# Advantech-Wise-1530-v1_0_0.net
KiCad netlist of a schematic drawn in EAGLE
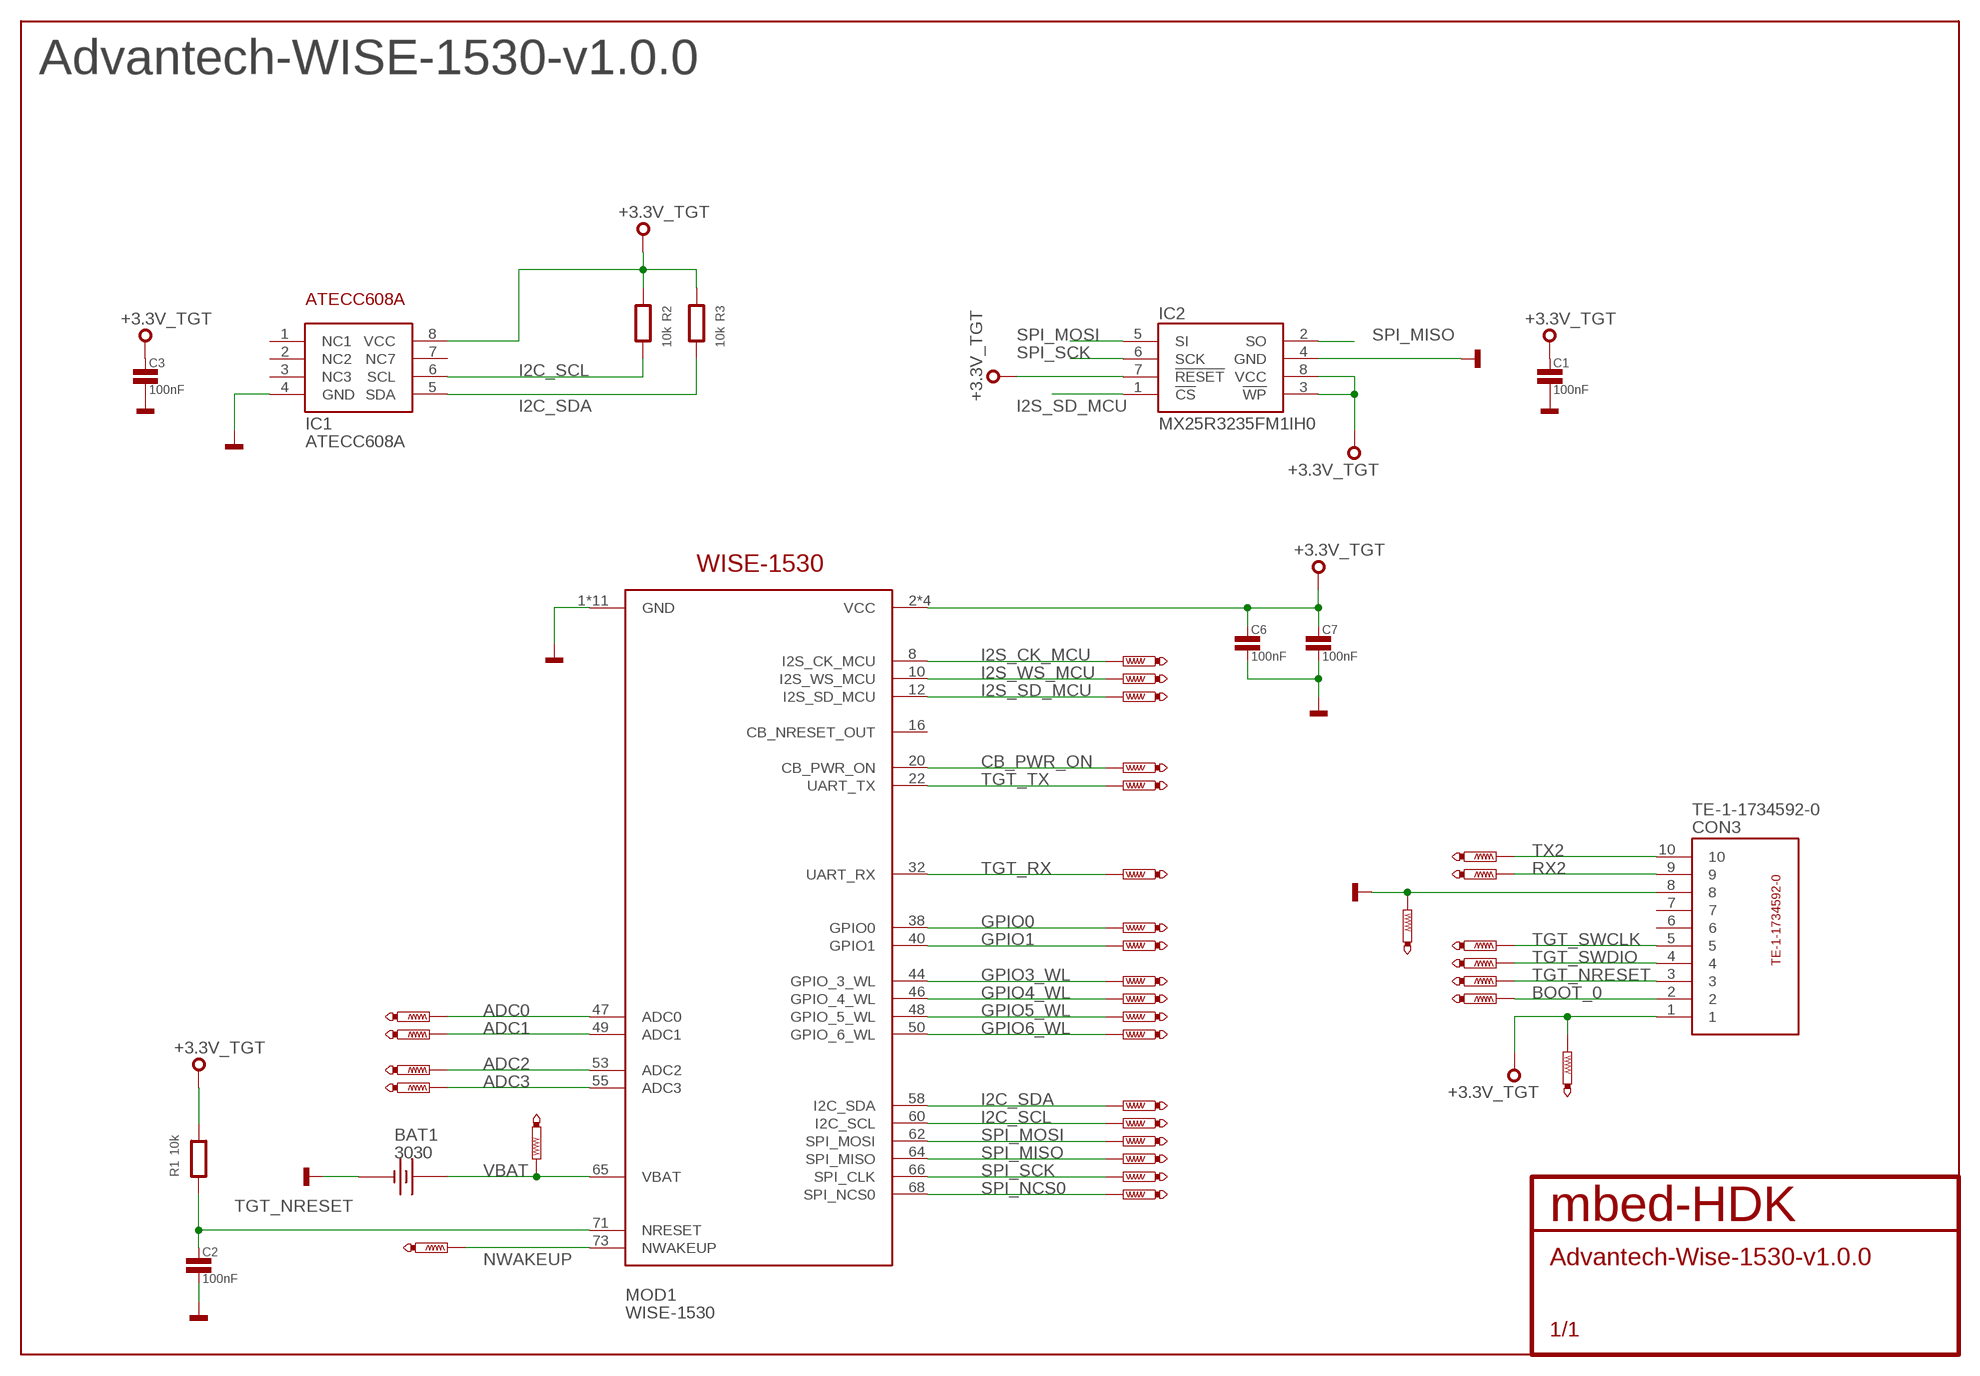
[diagram p0: schematic, sheet 1]

(export (version "E")
  (design (tool "Eeschema 10.0.6"))
  (components
    (comp (ref "BAT1")
      (value "3030")
      (footprint "eagle-import:3030")
      (fields (field (name "MF") "Keystone"))
      (libsource (lib "eagle-import") (part "3030"))
    )
    (comp (ref "C1")
      (value "100nF")
      (footprint "eagle-import:0603")
      (libsource (lib "eagle-import") (part "C0603"))
    )
    (comp (ref "C2")
      (value "100nF")
      (footprint "eagle-import:0603")
      (libsource (lib "eagle-import") (part "C0603"))
    )
    (comp (ref "C3")
      (value "100nF")
      (footprint "eagle-import:0603")
      (libsource (lib "eagle-import") (part "C0603"))
    )
    (comp (ref "C6")
      (value "100nF")
      (footprint "eagle-import:0603")
      (libsource (lib "eagle-import") (part "C0603"))
    )
    (comp (ref "C7")
      (value "100nF")
      (footprint "eagle-import:0603")
      (libsource (lib "eagle-import") (part "C0603"))
    )
    (comp (ref "CON3")
      (value "TE-1-1734592-0")
      (footprint "eagle-import:TE-1-1734592-0")
      (fields (field (name "MF") "TE Connectivity"))
      (libsource (lib "eagle-import") (part "TE-1-1734592-0"))
    )
    (comp (ref "IC1")
      (value "ATECC608A")
      (footprint "eagle-import:SO8")
      (fields (field (name "MF") "Atmel"))
      (libsource (lib "eagle-import") (part "ATECC608A"))
    )
    (comp (ref "IC2")
      (value "MX25R3235FM1IH0")
      (footprint "eagle-import:SO8")
      (fields (field (name "MF") "Macronix"))
      (libsource (lib "eagle-import") (part "MX25R3235FM1IH0"))
    )
    (comp (ref "MOD1")
      (value "WISE-1530")
      (footprint "eagle-import:MDT420E02001")
      (fields (field (name "MF") "Amphenol"))
      (libsource (lib "eagle-import") (part "WISE-1530"))
    )
    (comp (ref "R1")
      (value "10k")
      (footprint "eagle-import:0603")
      (libsource (lib "eagle-import") (part "R0603"))
    )
    (comp (ref "R2")
      (value "10k")
      (footprint "eagle-import:0603")
      (libsource (lib "eagle-import") (part "R0603"))
    )
    (comp (ref "R3")
      (value "10k")
      (footprint "eagle-import:0603")
      (libsource (lib "eagle-import") (part "R0603"))
    )
    (comp (ref "TP3")
      (value "PTR1TP08R")
      (footprint "eagle-import:TP08R")
      (libsource (lib "eagle-import") (part "PTR1TP08R"))
    )
    (comp (ref "TP4")
      (value "PTR1TP08R")
      (footprint "eagle-import:TP08R")
      (libsource (lib "eagle-import") (part "PTR1TP08R"))
    )
    (comp (ref "TP5")
      (value "PTR1TP08R")
      (footprint "eagle-import:TP08R")
      (libsource (lib "eagle-import") (part "PTR1TP08R"))
    )
    (comp (ref "TP6")
      (value "PTR1TP08R")
      (footprint "eagle-import:TP08R")
      (libsource (lib "eagle-import") (part "PTR1TP08R"))
    )
    (comp (ref "TP7")
      (value "PTR1TP08R")
      (footprint "eagle-import:TP08R")
      (libsource (lib "eagle-import") (part "PTR1TP08R"))
    )
    (comp (ref "TP8")
      (value "PTR1TP08R")
      (footprint "eagle-import:TP08R")
      (libsource (lib "eagle-import") (part "PTR1TP08R"))
    )
    (comp (ref "TP9")
      (value "PTR1TP08R")
      (footprint "eagle-import:TP08R")
      (libsource (lib "eagle-import") (part "PTR1TP08R"))
    )
    (comp (ref "TP10")
      (value "PTR1TP08R")
      (footprint "eagle-import:TP08R")
      (libsource (lib "eagle-import") (part "PTR1TP08R"))
    )
    (comp (ref "TP11")
      (value "PTR1TP08R")
      (footprint "eagle-import:TP08R")
      (libsource (lib "eagle-import") (part "PTR1TP08R"))
    )
    (comp (ref "TP12")
      (value "PTR1TP08R")
      (footprint "eagle-import:TP08R")
      (libsource (lib "eagle-import") (part "PTR1TP08R"))
    )
    (comp (ref "TP13")
      (value "PTR1TP08R")
      (footprint "eagle-import:TP08R")
      (libsource (lib "eagle-import") (part "PTR1TP08R"))
    )
    (comp (ref "TP14")
      (value "PTR1TP08R")
      (footprint "eagle-import:TP08R")
      (libsource (lib "eagle-import") (part "PTR1TP08R"))
    )
    (comp (ref "TP15")
      (value "PTR1TP08R")
      (footprint "eagle-import:TP08R")
      (libsource (lib "eagle-import") (part "PTR1TP08R"))
    )
    (comp (ref "TP16")
      (value "PTR1TP08R")
      (footprint "eagle-import:TP08R")
      (libsource (lib "eagle-import") (part "PTR1TP08R"))
    )
    (comp (ref "TP17")
      (value "PTR1TP08R")
      (footprint "eagle-import:TP08R")
      (libsource (lib "eagle-import") (part "PTR1TP08R"))
    )
    (comp (ref "TP18")
      (value "PTR1TP08R")
      (footprint "eagle-import:TP08R")
      (libsource (lib "eagle-import") (part "PTR1TP08R"))
    )
    (comp (ref "TP19")
      (value "PTR1TP08R")
      (footprint "eagle-import:TP08R")
      (libsource (lib "eagle-import") (part "PTR1TP08R"))
    )
    (comp (ref "TP20")
      (value "PTR1TP08R")
      (footprint "eagle-import:TP08R")
      (libsource (lib "eagle-import") (part "PTR1TP08R"))
    )
    (comp (ref "TP21")
      (value "PTR1TP08R")
      (footprint "eagle-import:TP08R")
      (libsource (lib "eagle-import") (part "PTR1TP08R"))
    )
    (comp (ref "TP22")
      (value "PTR1TP08R")
      (footprint "eagle-import:TP08R")
      (libsource (lib "eagle-import") (part "PTR1TP08R"))
    )
    (comp (ref "TP23")
      (value "PTR1TP08R")
      (footprint "eagle-import:TP08R")
      (libsource (lib "eagle-import") (part "PTR1TP08R"))
    )
    (comp (ref "TP24")
      (value "PTR1TP08R")
      (footprint "eagle-import:TP08R")
      (libsource (lib "eagle-import") (part "PTR1TP08R"))
    )
    (comp (ref "TP25")
      (value "PTR1TP08R")
      (footprint "eagle-import:TP08R")
      (libsource (lib "eagle-import") (part "PTR1TP08R"))
    )
    (comp (ref "TP26")
      (value "PTR1TP08R")
      (footprint "eagle-import:TP08R")
      (libsource (lib "eagle-import") (part "PTR1TP08R"))
    )
    (comp (ref "TP27")
      (value "PTR1TP08R")
      (footprint "eagle-import:TP08R")
      (libsource (lib "eagle-import") (part "PTR1TP08R"))
    )
    (comp (ref "TP28")
      (value "PTR1TP08R")
      (footprint "eagle-import:TP08R")
      (libsource (lib "eagle-import") (part "PTR1TP08R"))
    )
    (comp (ref "TP29")
      (value "PTR1TP08R")
      (footprint "eagle-import:TP08R")
      (libsource (lib "eagle-import") (part "PTR1TP08R"))
    )
    (comp (ref "TP30")
      (value "PTR1TP08R")
      (footprint "eagle-import:TP08R")
      (libsource (lib "eagle-import") (part "PTR1TP08R"))
    )
    (comp (ref "TP31")
      (value "PTR1TP08R")
      (footprint "eagle-import:TP08R")
      (libsource (lib "eagle-import") (part "PTR1TP08R"))
    )
    (comp (ref "TP32")
      (value "PTR1TP08R")
      (footprint "eagle-import:TP08R")
      (libsource (lib "eagle-import") (part "PTR1TP08R"))
    )
    (comp (ref "TP33")
      (value "PTR1TP08R")
      (footprint "eagle-import:TP08R")
      (libsource (lib "eagle-import") (part "PTR1TP08R"))
    )
    (comp (ref "TP34")
      (value "PTR1TP08R")
      (footprint "eagle-import:TP08R")
      (libsource (lib "eagle-import") (part "PTR1TP08R"))
    )
  )
  (nets
    (net (code "1") (name "+3.3V_TGT") (class "Default")
      (node (ref "C1") (pin "1") (pinfunction "P$1_1") (pintype "passive"))
      (node (ref "C3") (pin "1") (pinfunction "P$1_1") (pintype "passive"))
      (node (ref "C6") (pin "1") (pinfunction "P$1_1") (pintype "passive"))
      (node (ref "C7") (pin "1") (pinfunction "P$1_1") (pintype "passive"))
      (node (ref "CON3") (pin "1") (pinfunction "1_1") (pintype "bidirectional"))
      (node (ref "IC1") (pin "8") (pinfunction "VCC_8") (pintype "bidirectional"))
      (node (ref "IC2") (pin "3") (pinfunction "~{WP}_3") (pintype "bidirectional"))
      (node (ref "IC2") (pin "7") (pinfunction "~{RESET}_7") (pintype "bidirectional"))
      (node (ref "IC2") (pin "8") (pinfunction "VCC_8") (pintype "bidirectional"))
      (node (ref "MOD1") (pin "2") (pinfunction "VCC_2") (pintype "bidirectional"))
      (node (ref "MOD1") (pin "4") (pinfunction "VCC_4") (pintype "bidirectional"))
      (node (ref "MOD1") (pin "72") (pinfunction "VCC_72") (pintype "bidirectional"))
      (node (ref "MOD1") (pin "74") (pinfunction "VCC_74") (pintype "bidirectional"))
      (node (ref "R1") (pin "2") (pinfunction "P$2_2") (pintype "passive"))
      (node (ref "R2") (pin "1") (pinfunction "P$1_1") (pintype "passive"))
      (node (ref "R3") (pin "1") (pinfunction "P$1_1") (pintype "passive"))
      (node (ref "TP12") (pin "TP") (pinfunction "TP_TP") (pintype "input"))
    )
    (net (code "2") (name "/ADC0") (class "Default")
      (node (ref "MOD1") (pin "47") (pinfunction "ADC0_47") (pintype "bidirectional"))
      (node (ref "TP29") (pin "TP") (pinfunction "TP_TP") (pintype "input"))
    )
    (net (code "3") (name "/ADC1") (class "Default")
      (node (ref "MOD1") (pin "49") (pinfunction "ADC1_49") (pintype "bidirectional"))
      (node (ref "TP30") (pin "TP") (pinfunction "TP_TP") (pintype "input"))
    )
    (net (code "4") (name "/ADC2") (class "Default")
      (node (ref "MOD1") (pin "53") (pinfunction "ADC2_53") (pintype "bidirectional"))
      (node (ref "TP31") (pin "TP") (pinfunction "TP_TP") (pintype "input"))
    )
    (net (code "5") (name "/ADC3") (class "Default")
      (node (ref "MOD1") (pin "55") (pinfunction "ADC3_55") (pintype "bidirectional"))
      (node (ref "TP32") (pin "TP") (pinfunction "TP_TP") (pintype "input"))
    )
    (net (code "6") (name "/BOOT_0") (class "Default")
      (node (ref "CON3") (pin "2") (pinfunction "2_2") (pintype "bidirectional"))
      (node (ref "TP8") (pin "TP") (pinfunction "TP_TP") (pintype "input"))
    )
    (net (code "7") (name "/CB_PWR_ON") (class "Default")
      (node (ref "MOD1") (pin "20") (pinfunction "CB_PWR_ON_20") (pintype "bidirectional"))
      (node (ref "TP14") (pin "TP") (pinfunction "TP_TP") (pintype "input"))
    )
    (net (code "8") (name "/GPIO0") (class "Default")
      (node (ref "MOD1") (pin "38") (pinfunction "GPIO0_38") (pintype "bidirectional"))
      (node (ref "TP27") (pin "TP") (pinfunction "TP_TP") (pintype "input"))
    )
    (net (code "9") (name "/GPIO1") (class "Default")
      (node (ref "MOD1") (pin "40") (pinfunction "GPIO1_40") (pintype "bidirectional"))
      (node (ref "TP26") (pin "TP") (pinfunction "TP_TP") (pintype "input"))
    )
    (net (code "10") (name "/GPIO3_WL") (class "Default")
      (node (ref "MOD1") (pin "44") (pinfunction "GPIO_3_WL_44") (pintype "bidirectional"))
      (node (ref "TP25") (pin "TP") (pinfunction "TP_TP") (pintype "input"))
    )
    (net (code "11") (name "/GPIO4_WL") (class "Default")
      (node (ref "MOD1") (pin "46") (pinfunction "GPIO_4_WL_46") (pintype "bidirectional"))
      (node (ref "TP24") (pin "TP") (pinfunction "TP_TP") (pintype "input"))
    )
    (net (code "12") (name "/GPIO5_WL") (class "Default")
      (node (ref "MOD1") (pin "48") (pinfunction "GPIO_5_WL_48") (pintype "bidirectional"))
      (node (ref "TP23") (pin "TP") (pinfunction "TP_TP") (pintype "input"))
    )
    (net (code "13") (name "/GPIO6_WL") (class "Default")
      (node (ref "MOD1") (pin "50") (pinfunction "GPIO_6_WL_50") (pintype "bidirectional"))
      (node (ref "TP22") (pin "TP") (pinfunction "TP_TP") (pintype "input"))
    )
    (net (code "14") (name "/I2C_SCL") (class "Default")
      (node (ref "IC1") (pin "6") (pinfunction "SCL_6") (pintype "bidirectional"))
      (node (ref "MOD1") (pin "60") (pinfunction "I2C_SCL_60") (pintype "bidirectional"))
      (node (ref "R2") (pin "2") (pinfunction "P$2_2") (pintype "passive"))
      (node (ref "TP20") (pin "TP") (pinfunction "TP_TP") (pintype "input"))
    )
    (net (code "15") (name "/I2C_SDA") (class "Default")
      (node (ref "IC1") (pin "5") (pinfunction "SDA_5") (pintype "bidirectional"))
      (node (ref "MOD1") (pin "58") (pinfunction "I2C_SDA_58") (pintype "bidirectional"))
      (node (ref "R3") (pin "2") (pinfunction "P$2_2") (pintype "passive"))
      (node (ref "TP21") (pin "TP") (pinfunction "TP_TP") (pintype "input"))
    )
    (net (code "16") (name "/I2S_CK_MCU") (class "Default")
      (node (ref "MOD1") (pin "8") (pinfunction "I2S_CK_MCU_8") (pintype "bidirectional"))
      (node (ref "TP9") (pin "TP") (pinfunction "TP_TP") (pintype "input"))
    )
    (net (code "17") (name "/I2S_SD_MCU") (class "Default")
      (node (ref "IC2") (pin "1") (pinfunction "~{CS}_1") (pintype "bidirectional"))
      (node (ref "MOD1") (pin "12") (pinfunction "I2S_SD_MCU_12") (pintype "bidirectional"))
      (node (ref "TP11") (pin "TP") (pinfunction "TP_TP") (pintype "input"))
    )
    (net (code "18") (name "/I2S_WS_MCU") (class "Default")
      (node (ref "MOD1") (pin "10") (pinfunction "I2S_WS_MCU_10") (pintype "bidirectional"))
      (node (ref "TP10") (pin "TP") (pinfunction "TP_TP") (pintype "input"))
    )
    (net (code "19") (name "/NWAKEUP") (class "Default")
      (node (ref "MOD1") (pin "73") (pinfunction "NWAKEUP_73") (pintype "bidirectional"))
      (node (ref "TP34") (pin "TP") (pinfunction "TP_TP") (pintype "input"))
    )
    (net (code "20") (name "/RX2") (class "Default")
      (node (ref "CON3") (pin "9") (pinfunction "9_9") (pintype "bidirectional"))
      (node (ref "TP6") (pin "TP") (pinfunction "TP_TP") (pintype "input"))
    )
    (net (code "21") (name "/SPI_MISO") (class "Default")
      (node (ref "IC2") (pin "2") (pinfunction "SO_2") (pintype "bidirectional"))
      (node (ref "MOD1") (pin "64") (pinfunction "SPI_MISO_64") (pintype "bidirectional"))
      (node (ref "TP18") (pin "TP") (pinfunction "TP_TP") (pintype "input"))
    )
    (net (code "22") (name "/SPI_MOSI") (class "Default")
      (node (ref "IC2") (pin "5") (pinfunction "SI_5") (pintype "bidirectional"))
      (node (ref "MOD1") (pin "62") (pinfunction "SPI_MOSI_62") (pintype "bidirectional"))
      (node (ref "TP19") (pin "TP") (pinfunction "TP_TP") (pintype "input"))
    )
    (net (code "23") (name "/SPI_NCS0") (class "Default")
      (node (ref "MOD1") (pin "68") (pinfunction "SPI_NCS0_68") (pintype "bidirectional"))
      (node (ref "TP16") (pin "TP") (pinfunction "TP_TP") (pintype "input"))
    )
    (net (code "24") (name "/SPI_SCK") (class "Default")
      (node (ref "IC2") (pin "6") (pinfunction "SCK_6") (pintype "bidirectional"))
      (node (ref "MOD1") (pin "66") (pinfunction "SPI_CLK_66") (pintype "bidirectional"))
      (node (ref "TP17") (pin "TP") (pinfunction "TP_TP") (pintype "input"))
    )
    (net (code "25") (name "/TGT_NRESET") (class "Default")
      (node (ref "C2") (pin "1") (pinfunction "P$1_1") (pintype "passive"))
      (node (ref "CON3") (pin "3") (pinfunction "3_3") (pintype "bidirectional"))
      (node (ref "MOD1") (pin "71") (pinfunction "NRESET_71") (pintype "bidirectional"))
      (node (ref "R1") (pin "1") (pinfunction "P$1_1") (pintype "passive"))
      (node (ref "TP5") (pin "TP") (pinfunction "TP_TP") (pintype "input"))
    )
    (net (code "26") (name "/TGT_RX") (class "Default")
      (node (ref "MOD1") (pin "32") (pinfunction "UART_RX_32") (pintype "bidirectional"))
      (node (ref "TP28") (pin "TP") (pinfunction "TP_TP") (pintype "input"))
    )
    (net (code "27") (name "/TGT_SWCLK") (class "Default")
      (node (ref "CON3") (pin "5") (pinfunction "5_5") (pintype "bidirectional"))
      (node (ref "TP3") (pin "TP") (pinfunction "TP_TP") (pintype "input"))
    )
    (net (code "28") (name "/TGT_SWDIO") (class "Default")
      (node (ref "CON3") (pin "4") (pinfunction "4_4") (pintype "bidirectional"))
      (node (ref "TP4") (pin "TP") (pinfunction "TP_TP") (pintype "input"))
    )
    (net (code "29") (name "/TGT_TX") (class "Default")
      (node (ref "MOD1") (pin "22") (pinfunction "UART_TX_22") (pintype "bidirectional"))
      (node (ref "TP15") (pin "TP") (pinfunction "TP_TP") (pintype "input"))
    )
    (net (code "30") (name "/TX2") (class "Default")
      (node (ref "CON3") (pin "10") (pinfunction "10_10") (pintype "bidirectional"))
      (node (ref "TP7") (pin "TP") (pinfunction "TP_TP") (pintype "input"))
    )
    (net (code "31") (name "/VBAT") (class "Default")
      (node (ref "BAT1") (pin "P$1") (pinfunction "+_P$1") (pintype "bidirectional"))
      (node (ref "BAT1") (pin "P$2") (pinfunction "+_P$2") (pintype "bidirectional"))
      (node (ref "MOD1") (pin "65") (pinfunction "VBAT_65") (pintype "bidirectional"))
      (node (ref "TP33") (pin "TP") (pinfunction "TP_TP") (pintype "input"))
    )
    (net (code "32") (name "GND") (class "Default")
      (node (ref "BAT1") (pin "NEG") (pinfunction "-_NEG") (pintype "bidirectional"))
      (node (ref "C1") (pin "2") (pinfunction "P$2_2") (pintype "passive"))
      (node (ref "C2") (pin "2") (pinfunction "P$2_2") (pintype "passive"))
      (node (ref "C3") (pin "2") (pinfunction "P$2_2") (pintype "passive"))
      (node (ref "C6") (pin "2") (pinfunction "P$2_2") (pintype "passive"))
      (node (ref "C7") (pin "2") (pinfunction "P$2_2") (pintype "passive"))
      (node (ref "CON3") (pin "8") (pinfunction "8_8") (pintype "bidirectional"))
      (node (ref "IC1") (pin "4") (pinfunction "GND_4") (pintype "bidirectional"))
      (node (ref "IC2") (pin "4") (pinfunction "GND_4") (pintype "bidirectional"))
      (node (ref "MOD1") (pin "1") (pinfunction "GND_1") (pintype "bidirectional"))
      (node (ref "MOD1") (pin "18") (pinfunction "GND_18") (pintype "bidirectional"))
      (node (ref "MOD1") (pin "33") (pinfunction "GND_33") (pintype "bidirectional"))
      (node (ref "MOD1") (pin "39") (pinfunction "GND_39") (pintype "bidirectional"))
      (node (ref "MOD1") (pin "45") (pinfunction "GND_45") (pintype "bidirectional"))
      (node (ref "MOD1") (pin "51") (pinfunction "GND_51") (pintype "bidirectional"))
      (node (ref "MOD1") (pin "57") (pinfunction "GND_57") (pintype "bidirectional"))
      (node (ref "MOD1") (pin "63") (pinfunction "GND_63") (pintype "bidirectional"))
      (node (ref "MOD1") (pin "69") (pinfunction "GND_69") (pintype "bidirectional"))
      (node (ref "MOD1") (pin "7") (pinfunction "GND_7") (pintype "bidirectional"))
      (node (ref "MOD1") (pin "75") (pinfunction "GND_75") (pintype "bidirectional"))
      (node (ref "TP13") (pin "TP") (pinfunction "TP_TP") (pintype "input"))
    )
    (net (code "33") (name "unconnected-(CON3-Pad6)") (class "Default")
      (node (ref "CON3") (pin "6") (pinfunction "6_6") (pintype "bidirectional"))
    )
    (net (code "34") (name "unconnected-(CON3-Pad7)") (class "Default")
      (node (ref "CON3") (pin "7") (pinfunction "7_7") (pintype "bidirectional"))
    )
    (net (code "35") (name "unconnected-(IC1-NC1-Pad1)") (class "Default")
      (node (ref "IC1") (pin "1") (pinfunction "NC1_1") (pintype "bidirectional"))
    )
    (net (code "36") (name "unconnected-(IC1-NC2-Pad2)") (class "Default")
      (node (ref "IC1") (pin "2") (pinfunction "NC2_2") (pintype "bidirectional"))
    )
    (net (code "37") (name "unconnected-(IC1-NC3-Pad3)") (class "Default")
      (node (ref "IC1") (pin "3") (pinfunction "NC3_3") (pintype "bidirectional"))
    )
    (net (code "38") (name "unconnected-(IC1-NC7-Pad7)") (class "Default")
      (node (ref "IC1") (pin "7") (pinfunction "NC7_7") (pintype "bidirectional"))
    )
    (net (code "39") (name "unconnected-(MOD1-CB_NRESET_OUT-Pad16)") (class "Default")
      (node (ref "MOD1") (pin "16") (pinfunction "CB_NRESET_OUT_16") (pintype "bidirectional"))
    )
  )
)
